# KURTARMA.net
KiCad netlist of a schematic drawn in Altium Designer
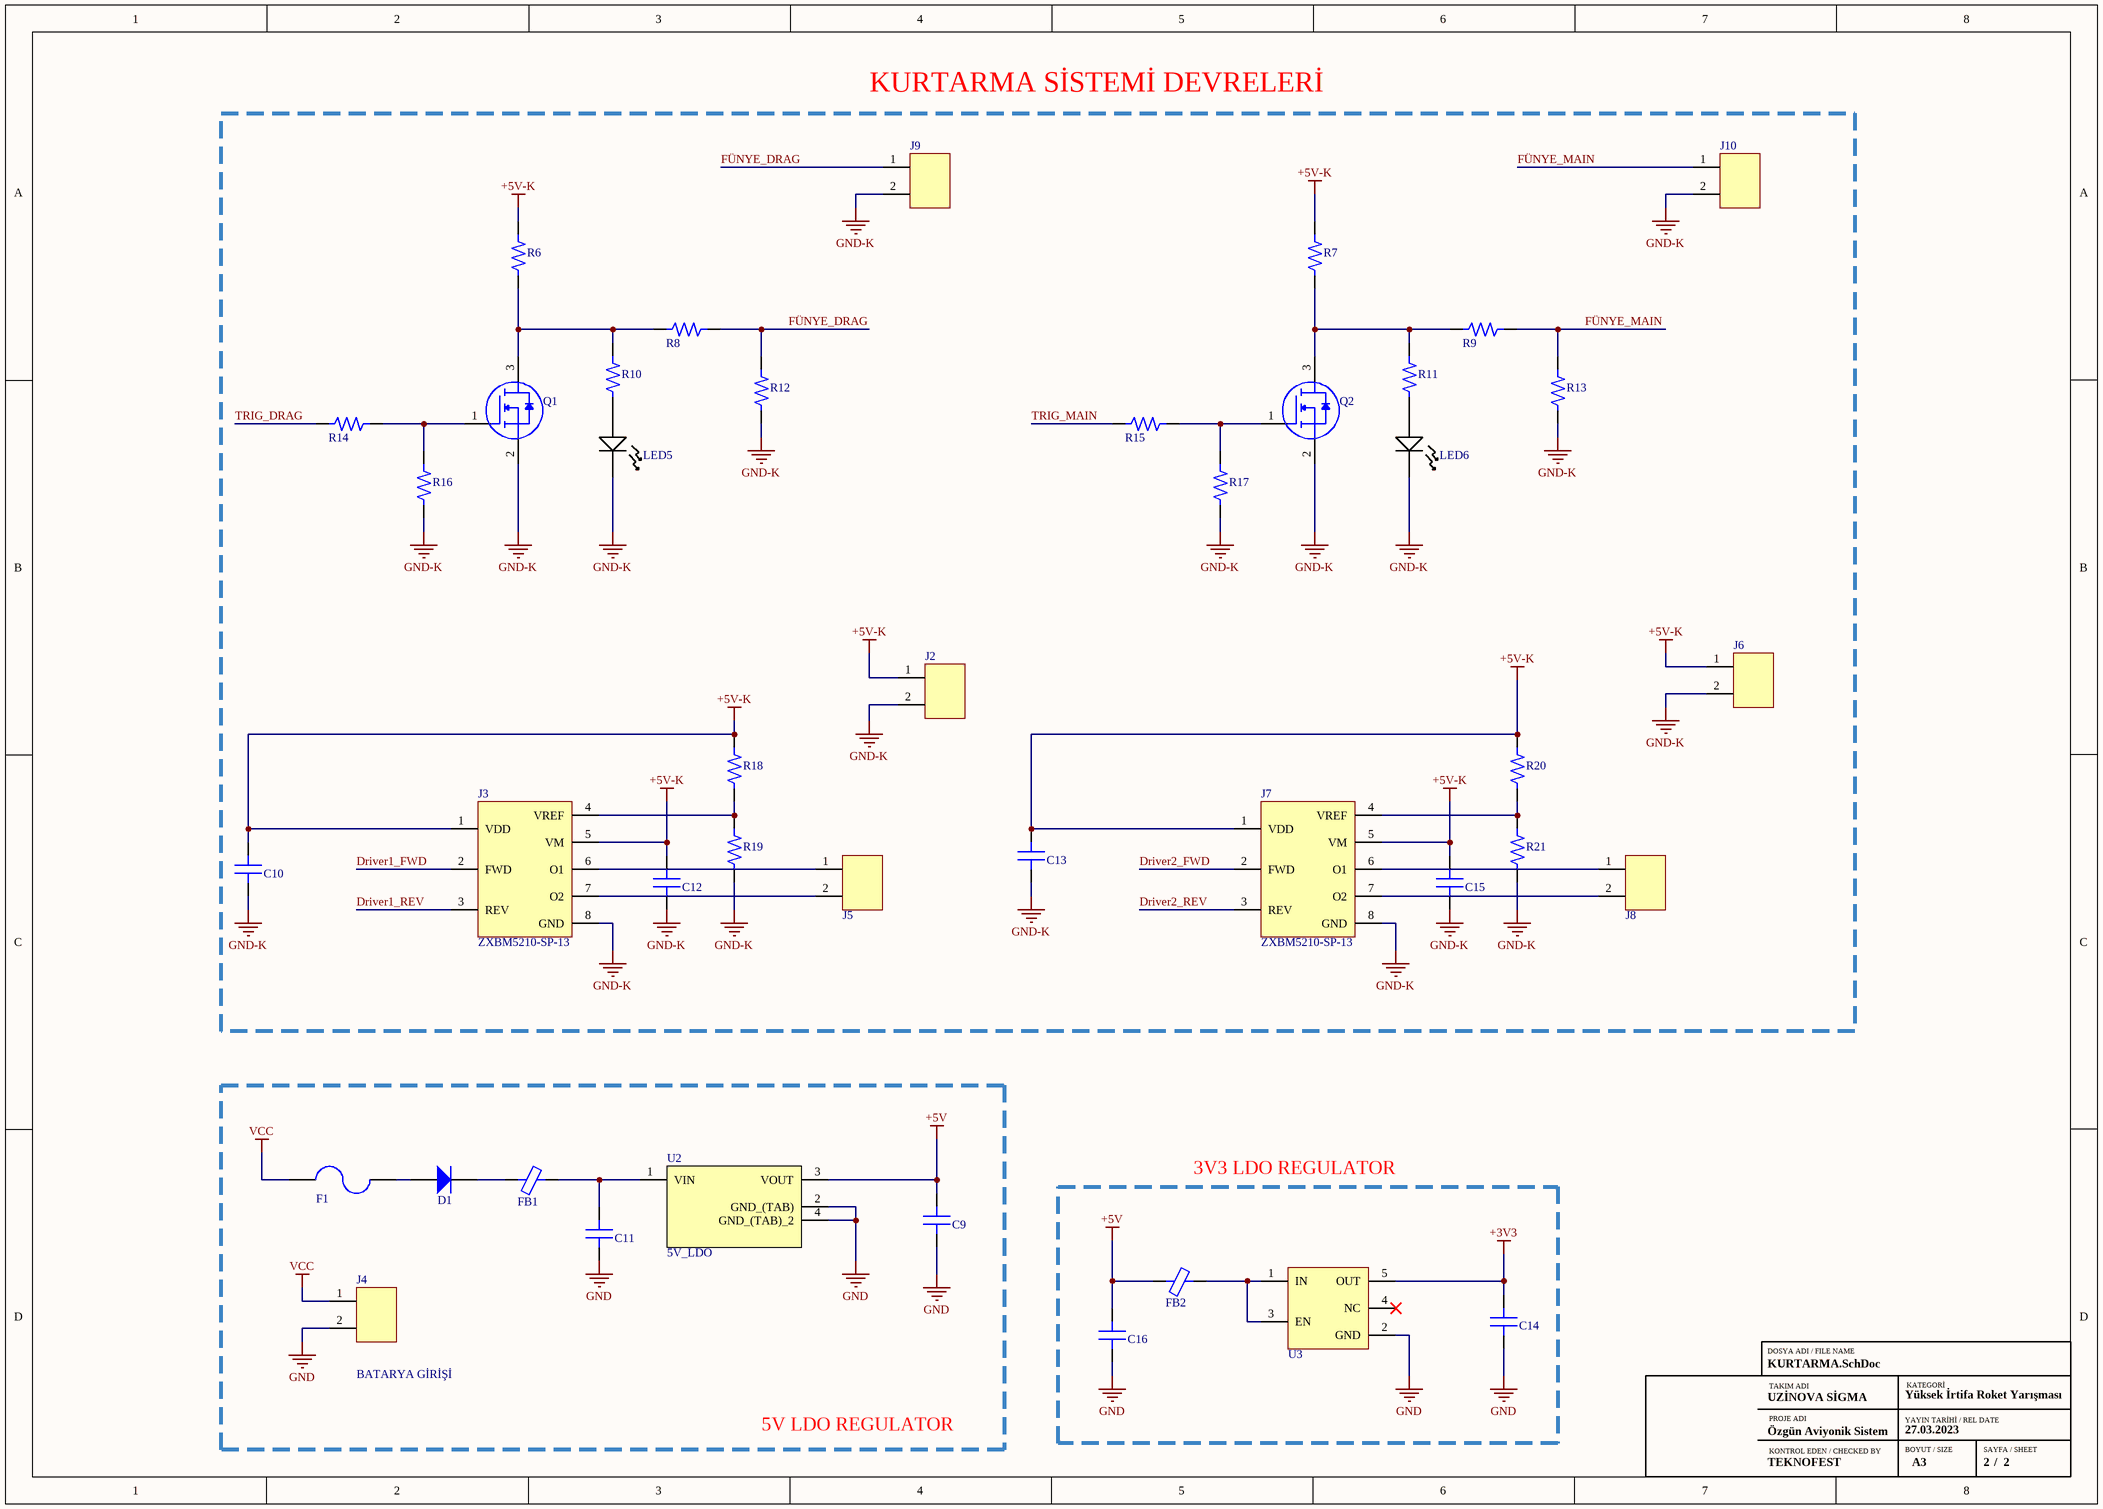
[diagram p0: KURTARMA.SchDoc]

(export (version "E")
  (design (tool "Eeschema 10.0.6"))
  (components
    (comp (ref "C9")
      (value "CAP CER 10uF 0805")
      (footprint "CAP_0805")
      (libsource (lib "ROKET_LIBRARY") (part "CAP CER 10uF 0805"))
    )
    (comp (ref "C10")
      (value "CAP CER 1uF 0805")
      (footprint "CAP_0805")
      (libsource (lib "ROKET_LIBRARY") (part "CAP CER 1uF 0805"))
    )
    (comp (ref "C11")
      (value "CAP CER 10uF 0805")
      (footprint "CAP_0805")
      (libsource (lib "ROKET_LIBRARY") (part "CAP CER 10uF 0805"))
    )
    (comp (ref "C12")
      (value "CAP CER 10uF 0805")
      (footprint "CAP_0805")
      (libsource (lib "ROKET_LIBRARY") (part "CAP CER 10uF 0805"))
    )
    (comp (ref "C13")
      (value "CAP CER 1uF 0805")
      (footprint "CAP_0805")
      (libsource (lib "ROKET_LIBRARY") (part "CAP CER 1uF 0805"))
    )
    (comp (ref "C14")
      (value "CAP CER 1uF 0805")
      (footprint "CAP_0805")
      (libsource (lib "ROKET_LIBRARY") (part "CAP CER 1uF 0805"))
    )
    (comp (ref "C15")
      (value "CAP CER 10uF 0805")
      (footprint "CAP_0805")
      (libsource (lib "ROKET_LIBRARY") (part "CAP CER 10uF 0805"))
    )
    (comp (ref "C16")
      (value "CAP CER 1uF 0805")
      (footprint "CAP_0805")
      (libsource (lib "ROKET_LIBRARY") (part "CAP CER 1uF 0805"))
    )
    (comp (ref "D1")
      (value "DIODE GEN PURP 75V 150MA SOD323F")
      (footprint "SOD323F")
      (description "VR=75V IF=150mA Trr=4ns P=200mW")
      (fields
        (field (name "MANUFACTURER") "ON Semiconductor / Fairchild")
        (field (name "MANUFACTURER PART NUMBER") "1N4148WS")
      )
      (libsource (lib "ROKET_LIBRARY") (part "DIODE"))
    )
    (comp (ref "F1")
      (value "FUSE 3413.0216.22")
      (footprint "FUSE_1206")
      (description "Fuse Chip Fast Acting 1A 32V SMD Solder Pad 1206 Glass T/R VDE/cULus")
      (fields
        (field (name "MANUFACTURER") "Schurter")
        (field (name "MANUFACTURER PART NUMBER") "3413.0216.22")
      )
      (libsource (lib "ROKET_LIBRARY") (part "FUSE"))
    )
    (comp (ref "FB1")
      (value "MPZ2012S601AT000")
      (footprint "FERRITE BEAD_0805")
      (description "0805 600Ω ±25% DCR=0.1Ω 2A")
      (fields (field (name "MANUFACTURER") "TDK"))
      (libsource (lib "ROKET_LIBRARY") (part "FERRITE BEAD"))
    )
    (comp (ref "FB2")
      (value "MPZ2012S601AT000")
      (footprint "FERRITE BEAD_0805")
      (description "0805 600Ω ±25% DCR=0.1Ω 2A")
      (fields (field (name "MANUFACTURER") "TDK"))
      (libsource (lib "ROKET_LIBRARY") (part "FERRITE BEAD"))
    )
    (comp (ref "J2")
      (value "Mike Connector")
      (footprint "MIKE CONNECTOR")
      (libsource (lib "ROKET_LIBRARY") (part "Mike Connector"))
    )
    (comp (ref "J3")
      (value "ZXBM5210-SP-13")
      (footprint "SO-8EP")
      (description "ZXBM5210 Series 18 V 1.5 A Reversible DC Motor Drive with Speed Control-SOIC-8EP")
      (fields (field (name "MANUFACTURER") "Diodes"))
      (libsource (lib "Roket_Library") (part "Driver"))
    )
    (comp (ref "J4")
      (value "Mike Connector")
      (footprint "MIKE CONNECTOR")
      (libsource (lib "ROKET_LIBRARY") (part "Mike Connector"))
    )
    (comp (ref "J5")
      (value "HEADER x2")
      (footprint "HEADER x2")
      (description "Conn Screw Type Terminal Block 2 POS 3.5mm Solder ST Thru-Hole 10A")
      (fields
        (field (name "MANUFACTURER") "On-Shore Technology")
        (field (name "MANUFACTURER PART NUMBER") "OSTTE020104")
      )
      (libsource (lib "ROKET_LIBRARY") (part "HEADER x2"))
    )
    (comp (ref "J6")
      (value "Mike Connector")
      (footprint "MIKE CONNECTOR")
      (libsource (lib "ROKET_LIBRARY") (part "Mike Connector"))
    )
    (comp (ref "J7")
      (value "ZXBM5210-SP-13")
      (footprint "SO-8EP")
      (description "ZXBM5210 Series 18 V 1.5 A Reversible DC Motor Drive with Speed Control-SOIC-8EP")
      (fields (field (name "MANUFACTURER") "Diodes"))
      (libsource (lib "Roket_Library") (part "Driver"))
    )
    (comp (ref "J8")
      (value "HEADER x2")
      (footprint "HEADER x2")
      (description "Conn Screw Type Terminal Block 2 POS 3.5mm Solder ST Thru-Hole 10A")
      (fields
        (field (name "MANUFACTURER") "On-Shore Technology")
        (field (name "MANUFACTURER PART NUMBER") "OSTTE020104")
      )
      (libsource (lib "ROKET_LIBRARY") (part "HEADER x2"))
    )
    (comp (ref "J9")
      (value "Mike Connector")
      (footprint "MIKE CONNECTOR")
      (libsource (lib "ROKET_LIBRARY") (part "Mike Connector"))
    )
    (comp (ref "J10")
      (value "Mike Connector")
      (footprint "MIKE CONNECTOR")
      (libsource (lib "ROKET_LIBRARY") (part "Mike Connector"))
    )
    (comp (ref "LED5")
      (value "CMD17-21VRD/TR8")
      (footprint "LED RED_0805")
      (description "LED Uni-Color Red 640nm 2-Pin SMT T/R")
      (fields (field (name "MANUFACTURER") "VCC CHML"))
      (libsource (lib "ROKET_LIBRARY") (part "LED RED"))
    )
    (comp (ref "LED6")
      (value "CMD17-21VRD/TR8")
      (footprint "LED RED_0805")
      (description "LED Uni-Color Red 640nm 2-Pin SMT T/R")
      (fields (field (name "MANUFACTURER") "VCC CHML"))
      (libsource (lib "ROKET_LIBRARY") (part "LED RED"))
    )
    (comp (ref "Q1")
      (value "NTR5103NT1G")
      (footprint "SOT-23-3")
      (description "MOSFET N-CH 60V 0.26A SOT23")
      (fields (field (name "MANUFACTURER") "ON Semiconductor"))
      (libsource (lib "ROKET_LIBRARY") (part "MOSFET N-Channel"))
    )
    (comp (ref "Q2")
      (value "NTR5103NT1G")
      (footprint "SOT-23-3")
      (description "MOSFET N-CH 60V 0.26A SOT23")
      (fields (field (name "MANUFACTURER") "ON Semiconductor"))
      (libsource (lib "ROKET_LIBRARY") (part "MOSFET N-Channel"))
    )
    (comp (ref "R6")
      (value "RES 0 OHM 0805")
      (footprint "RES_0805")
      (libsource (lib "ROKET_LIBRARY") (part "RES 0 OHM 0805"))
    )
    (comp (ref "R7")
      (value "RES 0 OHM 0805")
      (footprint "RES_0805")
      (libsource (lib "ROKET_LIBRARY") (part "RES 0 OHM 0805"))
    )
    (comp (ref "R8")
      (value "RES 20K OHM 0805")
      (footprint "RES_0805")
      (libsource (lib "ROKET_LIBRARY") (part "RES 20K OHM 0805"))
    )
    (comp (ref "R9")
      (value "RES 20K OHM 0805")
      (footprint "RES_0805")
      (libsource (lib "ROKET_LIBRARY") (part "RES 20K OHM 0805"))
    )
    (comp (ref "R10")
      (value "RES 470 OHM 0805")
      (footprint "RES_0805")
      (libsource (lib "ROKET_LIBRARY") (part "RES 470 OHM 0805"))
    )
    (comp (ref "R11")
      (value "RES 470 OHM 0805")
      (footprint "RES_0805")
      (libsource (lib "ROKET_LIBRARY") (part "RES 470 OHM 0805"))
    )
    (comp (ref "R12")
      (value "RES 10K OHM 0805")
      (footprint "RES_0805")
      (libsource (lib "ROKET_LIBRARY") (part "RES 10K OHM 0805"))
    )
    (comp (ref "R13")
      (value "RES 10K OHM 0805")
      (footprint "RES_0805")
      (libsource (lib "ROKET_LIBRARY") (part "RES 10K OHM 0805"))
    )
    (comp (ref "R14")
      (value "RES 1K OHM 0805")
      (footprint "RES_0805")
      (libsource (lib "ROKET_LIBRARY") (part "RES 1K OHM 0805"))
    )
    (comp (ref "R15")
      (value "RES 1K OHM 0805")
      (footprint "RES_0805")
      (libsource (lib "ROKET_LIBRARY") (part "RES 1K OHM 0805"))
    )
    (comp (ref "R16")
      (value "RES 10K OHM 0805")
      (footprint "RES_0805")
      (libsource (lib "ROKET_LIBRARY") (part "RES 10K OHM 0805"))
    )
    (comp (ref "R17")
      (value "RES 10K OHM 0805")
      (footprint "RES_0805")
      (libsource (lib "ROKET_LIBRARY") (part "RES 10K OHM 0805"))
    )
    (comp (ref "R18")
      (value "RES 1K OHM 0805")
      (footprint "RES_0805")
      (libsource (lib "ROKET_LIBRARY") (part "RES 1K OHM 0805"))
    )
    (comp (ref "R19")
      (value "RES 1K OHM 0805")
      (footprint "RES_0805")
      (libsource (lib "ROKET_LIBRARY") (part "RES 1K OHM 0805"))
    )
    (comp (ref "R20")
      (value "RES 1K OHM 0805")
      (footprint "RES_0805")
      (libsource (lib "ROKET_LIBRARY") (part "RES 1K OHM 0805"))
    )
    (comp (ref "R21")
      (value "RES 1K OHM 0805")
      (footprint "RES_0805")
      (libsource (lib "ROKET_LIBRARY") (part "RES 1K OHM 0805"))
    )
    (comp (ref "U2") (value "5V_LDO") (footprint "5V_LDO") (libsource (lib "ROKET_LIBRARY") (part "5V_LDO")))
    (comp (ref "U3")
      (value "NCP161ASN330T1G")
      (footprint "SOT-23-5")
      (description "LDO Regulator, 450 mA, Ultra-High PSRR, Ultra-Low Noise 3.3V, SOT23-5L, Active Discharge")
      (fields (field (name "MANUFACTURER") "ON Semiconductor"))
      (libsource (lib "ROKET_LIBRARY") (part "NCP161ASN330T1G"))
    )
  )
  (nets
    (net (code "1") (name "+3V3") (class "Default")
      (node (ref "C14") (pin "2") (pinfunction "2_2") (pintype "passive"))
      (node (ref "U3") (pin "5") (pinfunction "OUT_5") (pintype "passive"))
    )
    (net (code "2") (name "+5V") (class "Default")
      (node (ref "C16") (pin "2") (pinfunction "2_2") (pintype "passive"))
      (node (ref "C9") (pin "2") (pinfunction "2_2") (pintype "passive"))
      (node (ref "FB2") (pin "1") (pinfunction "1_1") (pintype "passive"))
      (node (ref "U2") (pin "3") (pinfunction "VOUT_3") (pintype "passive"))
    )
    (net (code "3") (name "+5V-K") (class "Default")
      (node (ref "C10") (pin "2") (pinfunction "2_2") (pintype "passive"))
      (node (ref "C12") (pin "2") (pinfunction "2_2") (pintype "passive"))
      (node (ref "C13") (pin "2") (pinfunction "2_2") (pintype "passive"))
      (node (ref "C15") (pin "2") (pinfunction "2_2") (pintype "passive"))
      (node (ref "J2") (pin "1") (pintype "passive"))
      (node (ref "J3") (pin "1") (pinfunction "VDD_1") (pintype "passive"))
      (node (ref "J3") (pin "5") (pinfunction "VM_5") (pintype "passive"))
      (node (ref "J6") (pin "1") (pintype "passive"))
      (node (ref "J7") (pin "1") (pinfunction "VDD_1") (pintype "passive"))
      (node (ref "J7") (pin "5") (pinfunction "VM_5") (pintype "passive"))
      (node (ref "R18") (pin "2") (pinfunction "2_2") (pintype "passive"))
      (node (ref "R20") (pin "2") (pinfunction "2_2") (pintype "passive"))
      (node (ref "R6") (pin "2") (pinfunction "2_2") (pintype "passive"))
      (node (ref "R7") (pin "2") (pinfunction "2_2") (pintype "passive"))
    )
    (net (code "4") (name "/Driver1_FWD") (class "Default")
      (node (ref "J3") (pin "2") (pinfunction "FWD_2") (pintype "passive"))
    )
    (net (code "5") (name "/Driver1_REV") (class "Default")
      (node (ref "J3") (pin "3") (pinfunction "REV_3") (pintype "passive"))
    )
    (net (code "6") (name "/Driver2_FWD") (class "Default")
      (node (ref "J7") (pin "2") (pinfunction "FWD_2") (pintype "passive"))
    )
    (net (code "7") (name "/Driver2_REV") (class "Default")
      (node (ref "J7") (pin "3") (pinfunction "REV_3") (pintype "passive"))
    )
    (net (code "8") (name "/FÜNYE_DRAG") (class "Default")
      (node (ref "J9") (pin "1") (pintype "passive"))
      (node (ref "R12") (pin "2") (pinfunction "2_2") (pintype "passive"))
      (node (ref "R8") (pin "2") (pinfunction "2_2") (pintype "passive"))
    )
    (net (code "9") (name "/FÜNYE_MAIN") (class "Default")
      (node (ref "J10") (pin "1") (pintype "passive"))
      (node (ref "R13") (pin "2") (pinfunction "2_2") (pintype "passive"))
      (node (ref "R9") (pin "2") (pinfunction "2_2") (pintype "passive"))
    )
    (net (code "10") (name "/TRIG_DRAG") (class "Default")
      (node (ref "R14") (pin "1") (pinfunction "1_1") (pintype "passive"))
    )
    (net (code "11") (name "/TRIG_MAIN") (class "Default")
      (node (ref "R15") (pin "1") (pinfunction "1_1") (pintype "passive"))
    )
    (net (code "12") (name "GND") (class "Default")
      (node (ref "C11") (pin "1") (pinfunction "1_1") (pintype "passive"))
      (node (ref "C14") (pin "1") (pinfunction "1_1") (pintype "passive"))
      (node (ref "C16") (pin "1") (pinfunction "1_1") (pintype "passive"))
      (node (ref "C9") (pin "1") (pinfunction "1_1") (pintype "passive"))
      (node (ref "J4") (pin "2") (pintype "passive"))
      (node (ref "U2") (pin "2") (pinfunction "GND_(TAB)_2") (pintype "passive"))
      (node (ref "U2") (pin "4") (pinfunction "GND_(TAB)_2_4") (pintype "passive"))
      (node (ref "U3") (pin "2") (pinfunction "GND_2") (pintype "passive"))
    )
    (net (code "13") (name "GND-K") (class "Default")
      (node (ref "C10") (pin "1") (pinfunction "1_1") (pintype "passive"))
      (node (ref "C12") (pin "1") (pinfunction "1_1") (pintype "passive"))
      (node (ref "C13") (pin "1") (pinfunction "1_1") (pintype "passive"))
      (node (ref "C15") (pin "1") (pinfunction "1_1") (pintype "passive"))
      (node (ref "J10") (pin "2") (pintype "passive"))
      (node (ref "J2") (pin "2") (pintype "passive"))
      (node (ref "J3") (pin "8") (pinfunction "GND_8") (pintype "passive"))
      (node (ref "J6") (pin "2") (pintype "passive"))
      (node (ref "J7") (pin "8") (pinfunction "GND_8") (pintype "passive"))
      (node (ref "J9") (pin "2") (pintype "passive"))
      (node (ref "LED5") (pin "2") (pinfunction "2_2") (pintype "passive"))
      (node (ref "LED6") (pin "2") (pinfunction "2_2") (pintype "passive"))
      (node (ref "Q1") (pin "2") (pinfunction "S_2") (pintype "passive"))
      (node (ref "Q2") (pin "2") (pinfunction "S_2") (pintype "passive"))
      (node (ref "R12") (pin "1") (pinfunction "1_1") (pintype "passive"))
      (node (ref "R13") (pin "1") (pinfunction "1_1") (pintype "passive"))
      (node (ref "R16") (pin "1") (pinfunction "1_1") (pintype "passive"))
      (node (ref "R17") (pin "1") (pinfunction "1_1") (pintype "passive"))
      (node (ref "R19") (pin "1") (pinfunction "1_1") (pintype "passive"))
      (node (ref "R21") (pin "1") (pinfunction "1_1") (pintype "passive"))
    )
    (net (code "14") (name "Net-(D1-ANODE)") (class "Default")
      (node (ref "D1") (pin "2") (pinfunction "ANODE_2") (pintype "passive"))
      (node (ref "F1") (pin "2") (pinfunction "2_2") (pintype "passive"))
    )
    (net (code "15") (name "Net-(D1-CATHODE)") (class "Default")
      (node (ref "D1") (pin "1") (pinfunction "CATHODE_1") (pintype "passive"))
      (node (ref "FB1") (pin "1") (pinfunction "1_1") (pintype "passive"))
    )
    (net (code "16") (name "Net-(J3-O1)") (class "Default")
      (node (ref "J3") (pin "6") (pinfunction "O1_6") (pintype "passive"))
      (node (ref "J5") (pin "1") (pinfunction "1_1") (pintype "passive"))
    )
    (net (code "17") (name "Net-(J3-O2)") (class "Default")
      (node (ref "J3") (pin "7") (pinfunction "O2_7") (pintype "passive"))
      (node (ref "J5") (pin "2") (pinfunction "2_2") (pintype "passive"))
    )
    (net (code "18") (name "Net-(J3-VREF)") (class "Default")
      (node (ref "J3") (pin "4") (pinfunction "VREF_4") (pintype "passive"))
      (node (ref "R18") (pin "1") (pinfunction "1_1") (pintype "passive"))
      (node (ref "R19") (pin "2") (pinfunction "2_2") (pintype "passive"))
    )
    (net (code "19") (name "Net-(J7-O1)") (class "Default")
      (node (ref "J7") (pin "6") (pinfunction "O1_6") (pintype "passive"))
      (node (ref "J8") (pin "1") (pinfunction "1_1") (pintype "passive"))
    )
    (net (code "20") (name "Net-(J7-O2)") (class "Default")
      (node (ref "J7") (pin "7") (pinfunction "O2_7") (pintype "passive"))
      (node (ref "J8") (pin "2") (pinfunction "2_2") (pintype "passive"))
    )
    (net (code "21") (name "Net-(J7-VREF)") (class "Default")
      (node (ref "J7") (pin "4") (pinfunction "VREF_4") (pintype "passive"))
      (node (ref "R20") (pin "1") (pinfunction "1_1") (pintype "passive"))
      (node (ref "R21") (pin "2") (pinfunction "2_2") (pintype "passive"))
    )
    (net (code "22") (name "Net-(LED5-Pad1)") (class "Default")
      (node (ref "LED5") (pin "1") (pinfunction "1_1") (pintype "passive"))
      (node (ref "R10") (pin "1") (pinfunction "1_1") (pintype "passive"))
    )
    (net (code "23") (name "Net-(LED6-Pad1)") (class "Default")
      (node (ref "LED6") (pin "1") (pinfunction "1_1") (pintype "passive"))
      (node (ref "R11") (pin "1") (pinfunction "1_1") (pintype "passive"))
    )
    (net (code "24") (name "Net-(Q1-D)") (class "Default")
      (node (ref "Q1") (pin "3") (pinfunction "D_3") (pintype "passive"))
      (node (ref "R10") (pin "2") (pinfunction "2_2") (pintype "passive"))
      (node (ref "R6") (pin "1") (pinfunction "1_1") (pintype "passive"))
      (node (ref "R8") (pin "1") (pinfunction "1_1") (pintype "passive"))
    )
    (net (code "25") (name "Net-(Q1-G)") (class "Default")
      (node (ref "Q1") (pin "1") (pinfunction "G_1") (pintype "passive"))
      (node (ref "R14") (pin "2") (pinfunction "2_2") (pintype "passive"))
      (node (ref "R16") (pin "2") (pinfunction "2_2") (pintype "passive"))
    )
    (net (code "26") (name "Net-(Q2-D)") (class "Default")
      (node (ref "Q2") (pin "3") (pinfunction "D_3") (pintype "passive"))
      (node (ref "R11") (pin "2") (pinfunction "2_2") (pintype "passive"))
      (node (ref "R7") (pin "1") (pinfunction "1_1") (pintype "passive"))
      (node (ref "R9") (pin "1") (pinfunction "1_1") (pintype "passive"))
    )
    (net (code "27") (name "Net-(Q2-G)") (class "Default")
      (node (ref "Q2") (pin "1") (pinfunction "G_1") (pintype "passive"))
      (node (ref "R15") (pin "2") (pinfunction "2_2") (pintype "passive"))
      (node (ref "R17") (pin "2") (pinfunction "2_2") (pintype "passive"))
    )
    (net (code "28") (name "Net-(U2-VIN)") (class "Default")
      (node (ref "C11") (pin "2") (pinfunction "2_2") (pintype "passive"))
      (node (ref "FB1") (pin "2") (pinfunction "2_2") (pintype "passive"))
      (node (ref "U2") (pin "1") (pinfunction "VIN_1") (pintype "passive"))
    )
    (net (code "29") (name "Net-(U3-EN)") (class "Default")
      (node (ref "FB2") (pin "2") (pinfunction "2_2") (pintype "passive"))
      (node (ref "U3") (pin "1") (pinfunction "IN_1") (pintype "passive"))
      (node (ref "U3") (pin "3") (pinfunction "EN_3") (pintype "passive"))
    )
    (net (code "30") (name "VCC") (class "Default")
      (node (ref "F1") (pin "1") (pinfunction "1_1") (pintype "passive"))
      (node (ref "J4") (pin "1") (pintype "passive"))
    )
    (net (code "31") (name "unconnected-(U3-NC-Pad4)") (class "Default")
      (node (ref "U3") (pin "4") (pinfunction "NC_4") (pintype "passive+no_connect"))
    )
  )
)
